# openSX70_ALPHA_V6-2-5-20181220.net
KiCad netlist of a schematic drawn in EAGLE
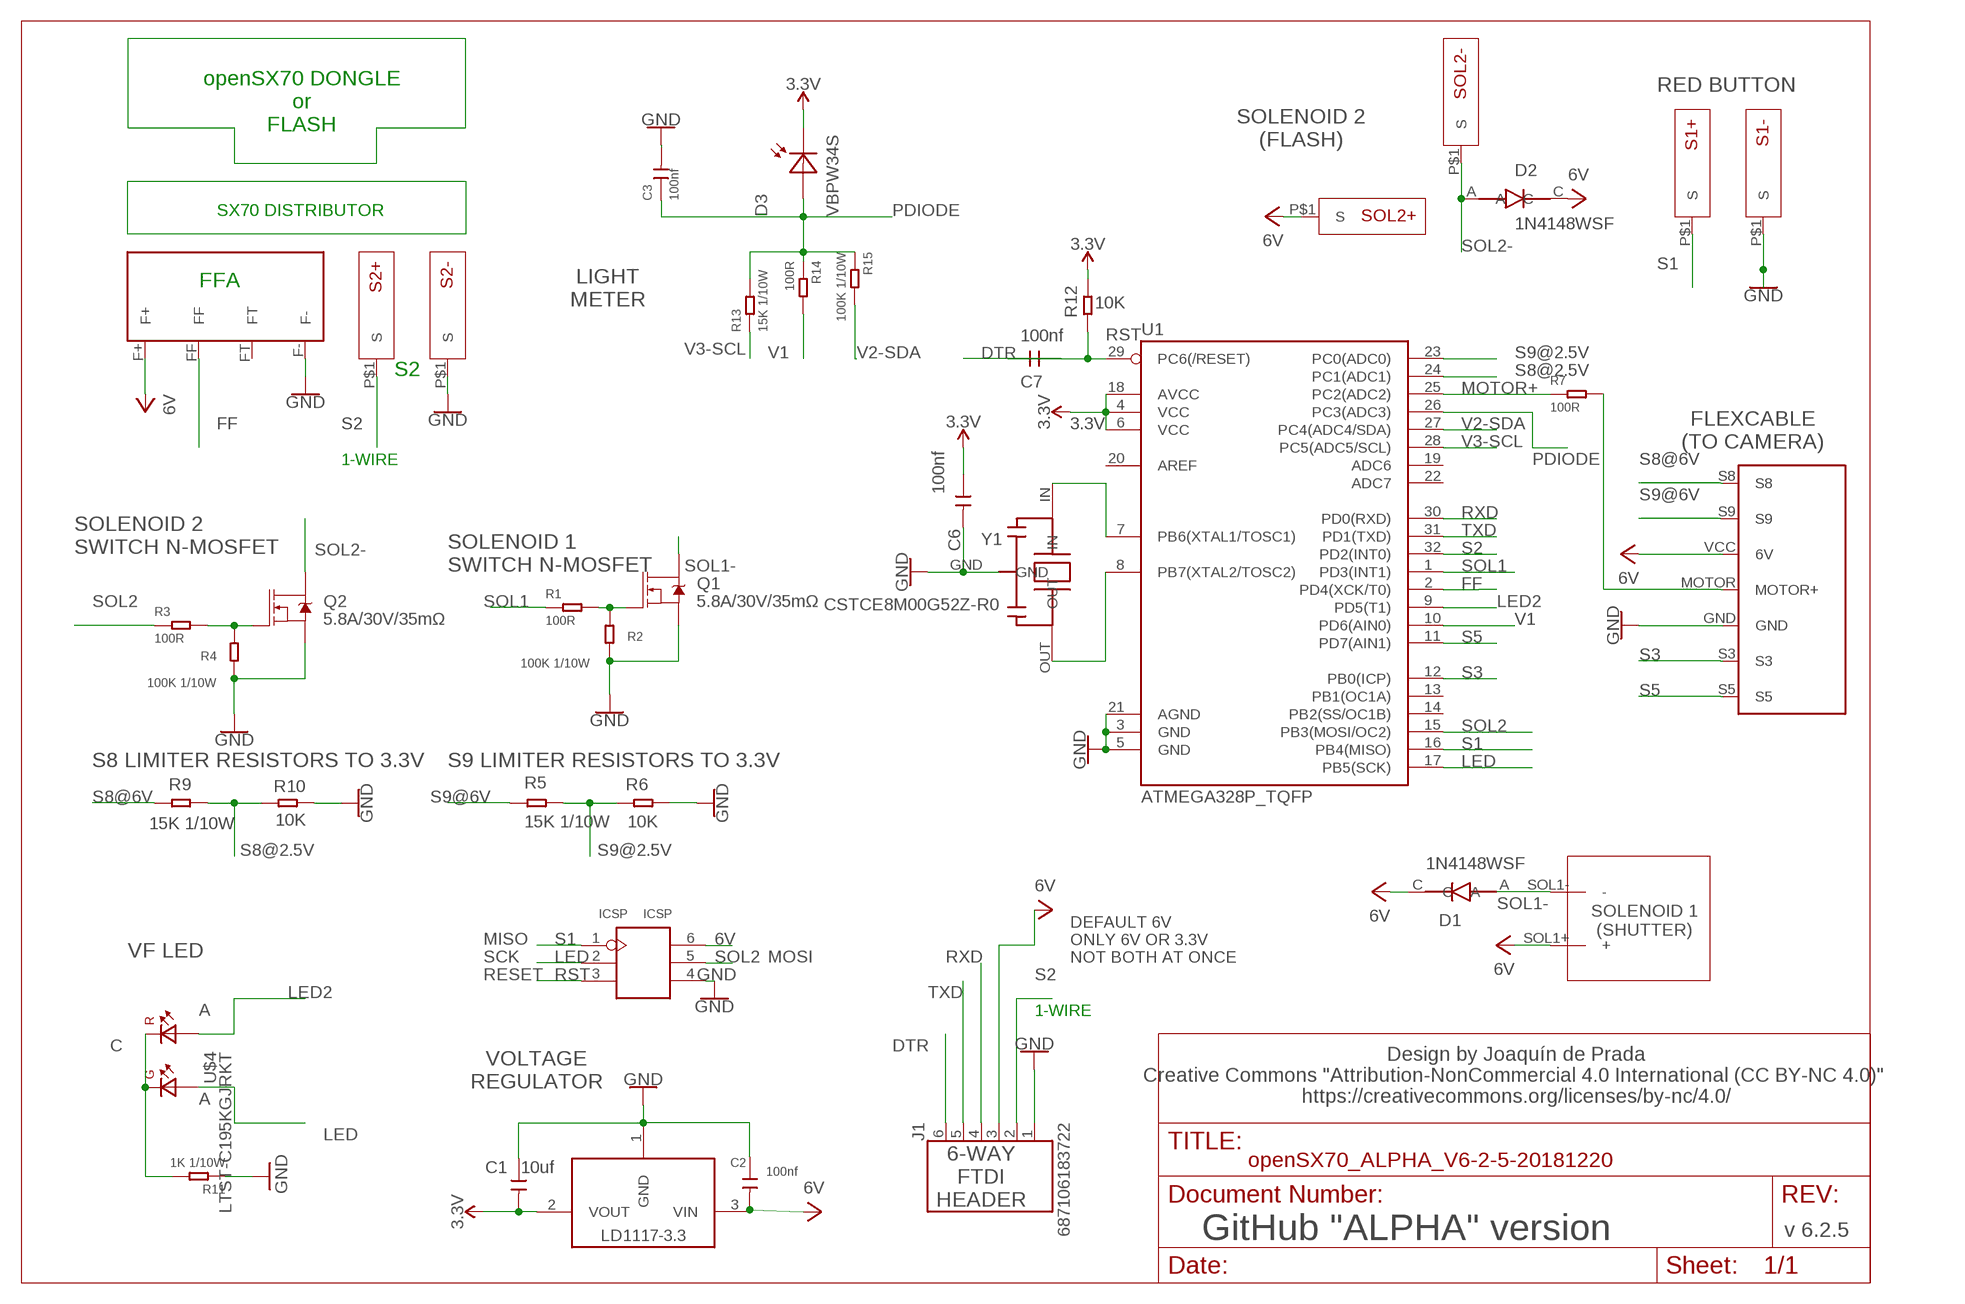
[diagram p0: schematic, sheet 1]

(export (version "E")
  (design (tool "Eeschema 10.0.6"))
  (components
    (comp (ref "C1")
      (value "10uf")
      (footprint "eagle-import:C0603")
      (fields (field (name "MPN") "CC0603KRX5R6BB106"))
      (libsource (lib "eagle-import") (part "CERAMIC-10UF-10V-10%-X5R(0603)"))
    )
    (comp (ref "C2")
      (value "100nf")
      (footprint "eagle-import:C0603")
      (fields (field (name "MPN") "CC0603KRX7R9BB104"))
      (libsource (lib "eagle-import") (part "CERAMIC-100NF-50V-10%-X7R(0603)"))
    )
    (comp (ref "C3")
      (value "100nf")
      (footprint "eagle-import:C0603")
      (fields (field (name "MPN") "CC0603KRX7R9BB104"))
      (libsource (lib "eagle-import") (part "CERAMIC-100NF-50V-10%-X7R(0603)"))
    )
    (comp (ref "C6")
      (value "100nf")
      (footprint "eagle-import:C0603")
      (fields (field (name "MPN") "CC0603KRX7R9BB104"))
      (libsource (lib "eagle-import") (part "CERAMIC-100NF-50V-10%-X7R(0603)"))
    )
    (comp (ref "C7")
      (value "100nf")
      (footprint "eagle-import:C0603")
      (fields (field (name "MPN") "CC0603KRX7R9BB104"))
      (libsource (lib "eagle-import") (part "CERAMIC-100NF-50V-10%-X7R(0603)"))
    )
    (comp (ref "D1")
      (value "1N4148WSF")
      (footprint "eagle-import:SODFL2512X100N")
      (fields (field (name "MANUFACTURER") "Fairchild Semiconductor"))
      (libsource (lib "eagle-import") (part "1N4148WS"))
    )
    (comp (ref "D2")
      (value "1N4148WSF")
      (footprint "eagle-import:SODFL2512X100N")
      (fields (field (name "MANUFACTURER") "Fairchild Semiconductor"))
      (libsource (lib "eagle-import") (part "1N4148WS"))
    )
    (comp (ref "D3")
      (value "VBPW34S")
      (footprint "eagle-import:SOD6439X130N")
      (fields (field (name "DIGI-KEY_PART_NUMBER") "751-1500-1-ND") (field (name "MF") "Vishay"))
      (libsource (lib "eagle-import") (part "VBPW34S"))
    )
    (comp (ref "ICSP")
      (value "ICSP")
      (footprint "eagle-import:H2X3-2.54")
      (libsource (lib "eagle-import") (part "ICSP"))
    )
    (comp (ref "J1")
      (value "687106183722")
      (footprint "eagle-import:687106183722")
      (fields (field (name "MF") "Wurth Electronics"))
      (libsource (lib "eagle-import") (part "687106183722"))
    )
    (comp (ref "LD11172.5V")
      (value "LD1117 2.5V")
      (footprint "eagle-import:SOT223")
      (fields (field (name "MF") "Advanced Monolithic Systems") (field (name "MP") "AMS1117-5.0"))
      (libsource (lib "eagle-import") (part "LD1117-3.3"))
    )
    (comp (ref "Q1")
      (value "5.8A/30V/35mΩ")
      (footprint "eagle-import:SOT23-3")
      (libsource (lib "eagle-import") (part "MOSFET-NCH-AO3404A"))
    )
    (comp (ref "Q2")
      (value "5.8A/30V/35mΩ")
      (footprint "eagle-import:SOT23-3")
      (libsource (lib "eagle-import") (part "MOSFET-NCH-AO3404A"))
    )
    (comp (ref "R1")
      (value "100R")
      (footprint "eagle-import:R0603")
      (fields (field (name "MPN") "RC0603JR-07100RL"))
      (libsource (lib "eagle-import") (part "SMD-RES-100R-5%-1/10W(0603)"))
    )
    (comp (ref "R2")
      (value "100K 1/10W")
      (footprint "eagle-import:R0603")
      (fields (field (name "MPN") "RC0603JR-07100KL"))
      (libsource (lib "eagle-import") (part "SMD-RES-100K-5%-1/10W(0603)"))
    )
    (comp (ref "R3")
      (value "100R")
      (footprint "eagle-import:R0603")
      (fields (field (name "MPN") "RC0603JR-07100RL"))
      (libsource (lib "eagle-import") (part "SMD-RES-100R-5%-1/10W(0603)"))
    )
    (comp (ref "R4")
      (value "100K 1/10W")
      (footprint "eagle-import:R0603")
      (fields (field (name "MPN") "RC0603JR-07100KL"))
      (libsource (lib "eagle-import") (part "SMD-RES-100K-5%-1/10W(0603)"))
    )
    (comp (ref "R5")
      (value "15K 1/10W")
      (footprint "eagle-import:R0603")
      (fields (field (name "MPN") "RC0603FR-0715KL"))
      (libsource (lib "eagle-import") (part "SMD-RES-15K-1%-1/10W(0603)"))
    )
    (comp (ref "R6")
      (value "10K")
      (footprint "eagle-import:R0603")
      (fields (field (name "MPN") "RC0603FR-0710KL"))
      (libsource (lib "eagle-import") (part "SMD-RES-10K-1%-1/10W(0603)"))
    )
    (comp (ref "R7")
      (value "100R")
      (footprint "eagle-import:R0603")
      (fields (field (name "MPN") "RC0603JR-07100RL"))
      (libsource (lib "eagle-import") (part "SMD-RES-100R-5%-1/10W(0603)"))
    )
    (comp (ref "R9")
      (value "15K 1/10W")
      (footprint "eagle-import:R0603")
      (fields (field (name "MPN") "RC0603FR-0715KL"))
      (libsource (lib "eagle-import") (part "SMD-RES-15K-1%-1/10W(0603)"))
    )
    (comp (ref "R10")
      (value "10K")
      (footprint "eagle-import:R0603")
      (fields (field (name "MPN") "RC0603FR-0710KL"))
      (libsource (lib "eagle-import") (part "SMD-RES-10K-1%-1/10W(0603)"))
    )
    (comp (ref "R11")
      (value "1K 1/10W")
      (footprint "eagle-import:R0603")
      (fields (field (name "MPN") "RC0603JR-071KL"))
      (libsource (lib "eagle-import") (part "SMD-RES-1K-5%-1/10W(0603)"))
    )
    (comp (ref "R12")
      (value "10K")
      (footprint "eagle-import:R0603")
      (fields (field (name "MPN") "RC0603FR-0710KL"))
      (libsource (lib "eagle-import") (part "SMD-RES-10K-1%-1/10W(0603)"))
    )
    (comp (ref "R13")
      (value "15K 1/10W")
      (footprint "eagle-import:R0603")
      (fields (field (name "MPN") "RC0603FR-0715KL"))
      (libsource (lib "eagle-import") (part "SMD-RES-15K-1%-1/10W(0603)"))
    )
    (comp (ref "R14")
      (value "100R")
      (footprint "eagle-import:R0603")
      (fields (field (name "MPN") "RC0603JR-07100RL"))
      (libsource (lib "eagle-import") (part "SMD-RES-100R-5%-1/10W(0603)"))
    )
    (comp (ref "R15")
      (value "100K 1/10W")
      (footprint "eagle-import:R0603")
      (fields (field (name "MPN") "RC0603JR-07100KL"))
      (libsource (lib "eagle-import") (part "SMD-RES-100K-5%-1/10W(0603)"))
    )
    (comp (ref "S1+")
      (value "SX70-S-PAD-NEW")
      (footprint "eagle-import:SX70-S-PAD2")
      (libsource (lib "eagle-import") (part "SX70-S-PAD-NEW"))
    )
    (comp (ref "S1-")
      (value "SX70-S-PAD-NEW")
      (footprint "eagle-import:SX70-S-PAD2")
      (libsource (lib "eagle-import") (part "SX70-S-PAD-NEW"))
    )
    (comp (ref "S2+")
      (value "SX70-S-PAD-NEW")
      (footprint "eagle-import:SX70-S-PAD2")
      (libsource (lib "eagle-import") (part "SX70-S-PAD-NEW"))
    )
    (comp (ref "S2-")
      (value "SX70-S-PAD-NEW")
      (footprint "eagle-import:SX70-S-PAD2")
      (libsource (lib "eagle-import") (part "SX70-S-PAD-NEW"))
    )
    (comp (ref "SOL1")
      (value "SX70-SOLENOID1-2PADS")
      (footprint "eagle-import:SX70-SOLENOID1-2")
      (libsource (lib "eagle-import") (part "SX70-SOLENOID1-2PADS"))
    )
    (comp (ref "SOL2+")
      (value "SX70-S-PAD-NEW")
      (footprint "eagle-import:SX70-S-PAD2")
      (libsource (lib "eagle-import") (part "SX70-S-PAD-NEW"))
    )
    (comp (ref "SOL2-")
      (value "SX70-S-PAD-NEW")
      (footprint "eagle-import:SX70-S-PAD2")
      (libsource (lib "eagle-import") (part "SX70-S-PAD-NEW"))
    )
    (comp (ref "U$1")
      (value "SX70-7-PAD")
      (footprint "eagle-import:SX70-7-PAD-PROPER")
      (libsource (lib "eagle-import") (part "SX70-7-PAD"))
    )
    (comp (ref "U$2")
      (value "FFA")
      (footprint "eagle-import:FFA-PAD-PACKAGE")
      (libsource (lib "eagle-import") (part "SX70-FFA-PAD"))
    )
    (comp (ref "U$4")
      (value "LTST-C195KGJRKT")
      (footprint "eagle-import:LTST-BILED-15X16")
      (fields (field (name "MF") "Lite-On Inc."))
      (libsource (lib "eagle-import") (part "LTST-C195KGJRKT"))
    )
    (comp (ref "U1")
      (value "ATMEGA328P_TQFP")
      (footprint "eagle-import:TQFP32-08")
      (libsource (lib "eagle-import") (part "ATMEGA328P_TQFP"))
    )
    (comp (ref "Y1")
      (value "CSTCE8M00G52Z-R0")
      (footprint "eagle-import:CFP95P160X100-3N")
      (fields (field (name "MF") "Murata") (field (name "MP") "CSTCE16M0V53-R0"))
      (libsource (lib "eagle-import") (part "CSTCE16M0V53-R0"))
    )
  )
  (nets
    (net (code "1") (name "/DTR") (class "Default")
      (node (ref "C7") (pin "1") (pinfunction "1_1") (pintype "passive"))
      (node (ref "J1") (pin "6") (pinfunction "1_6") (pintype "passive"))
    )
    (net (code "2") (name "/FF") (class "Default")
      (node (ref "U$2") (pin "FF") (pinfunction "FF_FF") (pintype "bidirectional"))
      (node (ref "U1") (pin "2") (pinfunction "PD4(XCK/T0)_2") (pintype "bidirectional"))
    )
    (net (code "3") (name "/LED") (class "Default")
      (node (ref "ICSP") (pin "2") (pinfunction "SCK_2") (pintype "bidirectional"))
      (node (ref "U$4") (pin "P$1") (pinfunction "A1_P$1") (pintype "passive"))
      (node (ref "U1") (pin "17") (pinfunction "PB5(SCK)_17") (pintype "bidirectional"))
    )
    (net (code "4") (name "/LED2") (class "Default")
      (node (ref "U$4") (pin "P$2") (pinfunction "A2_P$2") (pintype "passive"))
      (node (ref "U1") (pin "9") (pinfunction "PD5(T1)_9") (pintype "bidirectional"))
    )
    (net (code "5") (name "/MOTOR+") (class "Default")
      (node (ref "R7") (pin "1") (pinfunction "1_1") (pintype "passive"))
      (node (ref "U1") (pin "25") (pinfunction "PC2(ADC2)_25") (pintype "bidirectional"))
    )
    (net (code "6") (name "/PDIODE") (class "Default")
      (node (ref "C3") (pin "1") (pinfunction "1_1") (pintype "passive"))
      (node (ref "D3") (pin "A") (pinfunction "A_A") (pintype "passive"))
      (node (ref "R13") (pin "2") (pinfunction "2_2") (pintype "passive"))
      (node (ref "R14") (pin "1") (pinfunction "1_1") (pintype "passive"))
      (node (ref "R15") (pin "1") (pinfunction "1_1") (pintype "passive"))
      (node (ref "U1") (pin "26") (pinfunction "PC3(ADC3)_26") (pintype "bidirectional"))
    )
    (net (code "7") (name "/RST") (class "Default")
      (node (ref "C7") (pin "2") (pinfunction "2_2") (pintype "passive"))
      (node (ref "ICSP") (pin "3") (pinfunction "RST_3") (pintype "bidirectional"))
      (node (ref "R12") (pin "1") (pinfunction "1_1") (pintype "passive"))
      (node (ref "U1") (pin "29") (pinfunction "PC6(/RESET)_29") (pintype "bidirectional"))
    )
    (net (code "8") (name "/RXD") (class "Default")
      (node (ref "J1") (pin "4") (pinfunction "3_4") (pintype "passive"))
      (node (ref "U1") (pin "30") (pinfunction "PD0(RXD)_30") (pintype "bidirectional"))
    )
    (net (code "9") (name "/S1") (class "Default")
      (node (ref "ICSP") (pin "1") (pinfunction "MISO_1") (pintype "bidirectional"))
      (node (ref "S1+") (pin "P$1") (pinfunction "S_P$1") (pintype "bidirectional"))
      (node (ref "U1") (pin "16") (pinfunction "PB4(MISO)_16") (pintype "bidirectional"))
    )
    (net (code "10") (name "/S2") (class "Default")
      (node (ref "J1") (pin "2") (pinfunction "5_2") (pintype "passive"))
      (node (ref "S2+") (pin "P$1") (pinfunction "S_P$1") (pintype "bidirectional"))
      (node (ref "U1") (pin "32") (pinfunction "PD2(INT0)_32") (pintype "bidirectional"))
    )
    (net (code "11") (name "/S3") (class "Default")
      (node (ref "U$1") (pin "S3") (pinfunction "S3_S3") (pintype "bidirectional"))
      (node (ref "U1") (pin "12") (pinfunction "PB0(ICP)_12") (pintype "bidirectional"))
    )
    (net (code "12") (name "/S5") (class "Default")
      (node (ref "U$1") (pin "S5") (pinfunction "S5_S5") (pintype "bidirectional"))
      (node (ref "U1") (pin "11") (pinfunction "PD7(AIN1)_11") (pintype "bidirectional"))
    )
    (net (code "13") (name "/S8@2.5V") (class "Default")
      (node (ref "R10") (pin "1") (pinfunction "1_1") (pintype "passive"))
      (node (ref "R9") (pin "2") (pinfunction "2_2") (pintype "passive"))
      (node (ref "U1") (pin "24") (pinfunction "PC1(ADC1)_24") (pintype "bidirectional"))
    )
    (net (code "14") (name "/S8@6V") (class "Default")
      (node (ref "R9") (pin "1") (pinfunction "1_1") (pintype "passive"))
      (node (ref "U$1") (pin "S8") (pinfunction "S8_S8") (pintype "bidirectional"))
    )
    (net (code "15") (name "/S9@2.5V") (class "Default")
      (node (ref "R5") (pin "2") (pinfunction "2_2") (pintype "passive"))
      (node (ref "R6") (pin "1") (pinfunction "1_1") (pintype "passive"))
      (node (ref "U1") (pin "23") (pinfunction "PC0(ADC0)_23") (pintype "bidirectional"))
    )
    (net (code "16") (name "/S9@6V") (class "Default")
      (node (ref "R5") (pin "1") (pinfunction "1_1") (pintype "passive"))
      (node (ref "U$1") (pin "S9") (pinfunction "S9_S9") (pintype "bidirectional"))
    )
    (net (code "17") (name "/SOL1") (class "Default")
      (node (ref "R1") (pin "1") (pinfunction "1_1") (pintype "passive"))
      (node (ref "U1") (pin "1") (pinfunction "PD3(INT1)_1") (pintype "bidirectional"))
    )
    (net (code "18") (name "/SOL1-") (class "Default")
      (node (ref "D1") (pin "A") (pinfunction "A_A") (pintype "passive"))
      (node (ref "Q1") (pin "3") (pinfunction "D_3") (pintype "bidirectional"))
      (node (ref "SOL1") (pin "SOL1-") (pinfunction "-_SOL1-") (pintype "bidirectional"))
    )
    (net (code "19") (name "/SOL2") (class "Default")
      (node (ref "ICSP") (pin "5") (pinfunction "MOSI_5") (pintype "bidirectional"))
      (node (ref "R3") (pin "1") (pinfunction "1_1") (pintype "passive"))
      (node (ref "U1") (pin "15") (pinfunction "PB3(MOSI/OC2)_15") (pintype "bidirectional"))
    )
    (net (code "20") (name "/SOL2-") (class "Default")
      (node (ref "D2") (pin "A") (pinfunction "A_A") (pintype "passive"))
      (node (ref "Q2") (pin "3") (pinfunction "D_3") (pintype "bidirectional"))
      (node (ref "SOL2-") (pin "P$1") (pinfunction "S_P$1") (pintype "bidirectional"))
    )
    (net (code "21") (name "/TXD") (class "Default")
      (node (ref "J1") (pin "5") (pinfunction "2_5") (pintype "passive"))
      (node (ref "U1") (pin "31") (pinfunction "PD1(TXD)_31") (pintype "bidirectional"))
    )
    (net (code "22") (name "/V1") (class "Default")
      (node (ref "R14") (pin "2") (pinfunction "2_2") (pintype "passive"))
      (node (ref "U1") (pin "10") (pinfunction "PD6(AIN0)_10") (pintype "bidirectional"))
    )
    (net (code "23") (name "/V2-SDA") (class "Default")
      (node (ref "R15") (pin "2") (pinfunction "2_2") (pintype "passive"))
      (node (ref "U1") (pin "27") (pinfunction "PC4(ADC4/SDA)_27") (pintype "bidirectional"))
    )
    (net (code "24") (name "/V3-SCL") (class "Default")
      (node (ref "R13") (pin "1") (pinfunction "1_1") (pintype "passive"))
      (node (ref "U1") (pin "28") (pinfunction "PC5(ADC5/SCL)_28") (pintype "bidirectional"))
    )
    (net (code "25") (name "3.3V") (class "Default")
      (node (ref "C1") (pin "2") (pinfunction "2_2") (pintype "passive"))
      (node (ref "C6") (pin "1") (pinfunction "1_1") (pintype "passive"))
      (node (ref "D3") (pin "C") (pinfunction "C_C") (pintype "passive"))
      (node (ref "LD11172.5V") (pin "2") (pinfunction "VOUT_2") (pintype "bidirectional"))
      (node (ref "R12") (pin "2") (pinfunction "2_2") (pintype "passive"))
      (node (ref "U1") (pin "18") (pinfunction "AVCC_18") (pintype "bidirectional"))
      (node (ref "U1") (pin "4") (pinfunction "VCC_4") (pintype "bidirectional"))
      (node (ref "U1") (pin "6") (pinfunction "VCC_6") (pintype "bidirectional"))
    )
    (net (code "26") (name "6V") (class "Default")
      (node (ref "C2") (pin "2") (pinfunction "2_2") (pintype "passive"))
      (node (ref "D1") (pin "C") (pinfunction "C_C") (pintype "passive"))
      (node (ref "D2") (pin "C") (pinfunction "C_C") (pintype "passive"))
      (node (ref "ICSP") (pin "6") (pinfunction "VCC_6") (pintype "bidirectional"))
      (node (ref "J1") (pin "3") (pinfunction "4_3") (pintype "passive"))
      (node (ref "LD11172.5V") (pin "3") (pinfunction "VIN_3") (pintype "bidirectional"))
      (node (ref "SOL1") (pin "SOL1+") (pinfunction "+_SOL1+") (pintype "bidirectional"))
      (node (ref "SOL2+") (pin "P$1") (pinfunction "S_P$1") (pintype "bidirectional"))
      (node (ref "U$1") (pin "VCC") (pinfunction "6V_VCC") (pintype "bidirectional"))
      (node (ref "U$2") (pin "F+") (pinfunction "F+_F+") (pintype "bidirectional"))
    )
    (net (code "27") (name "GND") (class "Default")
      (node (ref "C1") (pin "1") (pinfunction "1_1") (pintype "passive"))
      (node (ref "C2") (pin "1") (pinfunction "1_1") (pintype "passive"))
      (node (ref "C3") (pin "2") (pinfunction "2_2") (pintype "passive"))
      (node (ref "C6") (pin "2") (pinfunction "2_2") (pintype "passive"))
      (node (ref "ICSP") (pin "4") (pinfunction "GND_4") (pintype "bidirectional"))
      (node (ref "J1") (pin "1") (pinfunction "6_1") (pintype "passive"))
      (node (ref "LD11172.5V") (pin "1") (pinfunction "GND_1") (pintype "bidirectional"))
      (node (ref "Q1") (pin "2") (pinfunction "S_2") (pintype "bidirectional"))
      (node (ref "Q2") (pin "2") (pinfunction "S_2") (pintype "bidirectional"))
      (node (ref "R10") (pin "2") (pinfunction "2_2") (pintype "passive"))
      (node (ref "R11") (pin "1") (pinfunction "1_1") (pintype "passive"))
      (node (ref "R2") (pin "1") (pinfunction "1_1") (pintype "passive"))
      (node (ref "R4") (pin "1") (pinfunction "1_1") (pintype "passive"))
      (node (ref "R6") (pin "2") (pinfunction "2_2") (pintype "passive"))
      (node (ref "S1-") (pin "P$1") (pinfunction "S_P$1") (pintype "bidirectional"))
      (node (ref "S2-") (pin "P$1") (pinfunction "S_P$1") (pintype "bidirectional"))
      (node (ref "U$1") (pin "GND") (pinfunction "GND_GND") (pintype "bidirectional"))
      (node (ref "U$2") (pin "F-") (pinfunction "F-_F-") (pintype "bidirectional"))
      (node (ref "U1") (pin "21") (pinfunction "AGND_21") (pintype "bidirectional"))
      (node (ref "U1") (pin "3") (pinfunction "GND_3") (pintype "bidirectional"))
      (node (ref "U1") (pin "5") (pinfunction "GND_5") (pintype "bidirectional"))
      (node (ref "Y1") (pin "GND") (pinfunction "GND_GND") (pintype "passive"))
    )
    (net (code "28") (name "Net-(Q1-G)") (class "Default")
      (node (ref "Q1") (pin "1") (pinfunction "G_1") (pintype "bidirectional"))
      (node (ref "R1") (pin "2") (pinfunction "2_2") (pintype "passive"))
      (node (ref "R2") (pin "2") (pinfunction "2_2") (pintype "passive"))
    )
    (net (code "29") (name "Net-(Q2-G)") (class "Default")
      (node (ref "Q2") (pin "1") (pinfunction "G_1") (pintype "bidirectional"))
      (node (ref "R3") (pin "2") (pinfunction "2_2") (pintype "passive"))
      (node (ref "R4") (pin "2") (pinfunction "2_2") (pintype "passive"))
    )
    (net (code "30") (name "Net-(U$1-MOTOR+)") (class "Default")
      (node (ref "R7") (pin "2") (pinfunction "2_2") (pintype "passive"))
      (node (ref "U$1") (pin "MOTOR") (pinfunction "MOTOR+_MOTOR") (pintype "bidirectional"))
    )
    (net (code "31") (name "Net-(U$4-K1)") (class "Default")
      (node (ref "R11") (pin "2") (pinfunction "2_2") (pintype "passive"))
      (node (ref "U$4") (pin "P$3") (pinfunction "K1_P$3") (pintype "passive"))
      (node (ref "U$4") (pin "P$4") (pinfunction "K2_P$4") (pintype "passive"))
    )
    (net (code "32") (name "Net-(U1-PB6(XTAL1{slash}TOSC1))") (class "Default")
      (node (ref "U1") (pin "7") (pinfunction "PB6(XTAL1/TOSC1)_7") (pintype "bidirectional"))
      (node (ref "Y1") (pin "IN") (pinfunction "IN_IN") (pintype "input"))
    )
    (net (code "33") (name "Net-(U1-PB7(XTAL2{slash}TOSC2))") (class "Default")
      (node (ref "U1") (pin "8") (pinfunction "PB7(XTAL2/TOSC2)_8") (pintype "bidirectional"))
      (node (ref "Y1") (pin "OUT") (pinfunction "OUT_OUT") (pintype "output"))
    )
    (net (code "34") (name "unconnected-(U$2-PadFT)") (class "Default")
      (node (ref "U$2") (pin "FT") (pinfunction "FT_FT") (pintype "bidirectional"))
    )
    (net (code "35") (name "unconnected-(U1-ADC6-Pad19)") (class "Default")
      (node (ref "U1") (pin "19") (pinfunction "ADC6_19") (pintype "bidirectional"))
    )
    (net (code "36") (name "unconnected-(U1-ADC7-Pad22)") (class "Default")
      (node (ref "U1") (pin "22") (pinfunction "ADC7_22") (pintype "bidirectional"))
    )
    (net (code "37") (name "unconnected-(U1-AREF-Pad20)") (class "Default")
      (node (ref "U1") (pin "20") (pinfunction "AREF_20") (pintype "bidirectional"))
    )
    (net (code "38") (name "unconnected-(U1-PB1(OC1A)-Pad13)") (class "Default")
      (node (ref "U1") (pin "13") (pinfunction "PB1(OC1A)_13") (pintype "bidirectional"))
    )
    (net (code "39") (name "unconnected-(U1-PB2(SS{slash}OC1B)-Pad14)") (class "Default")
      (node (ref "U1") (pin "14") (pinfunction "PB2(SS/OC1B)_14") (pintype "bidirectional"))
    )
  )
)
